# SparkFun_Digi_XBee_Regulated_Qwiic.net
KiCad netlist of a schematic drawn in EAGLE
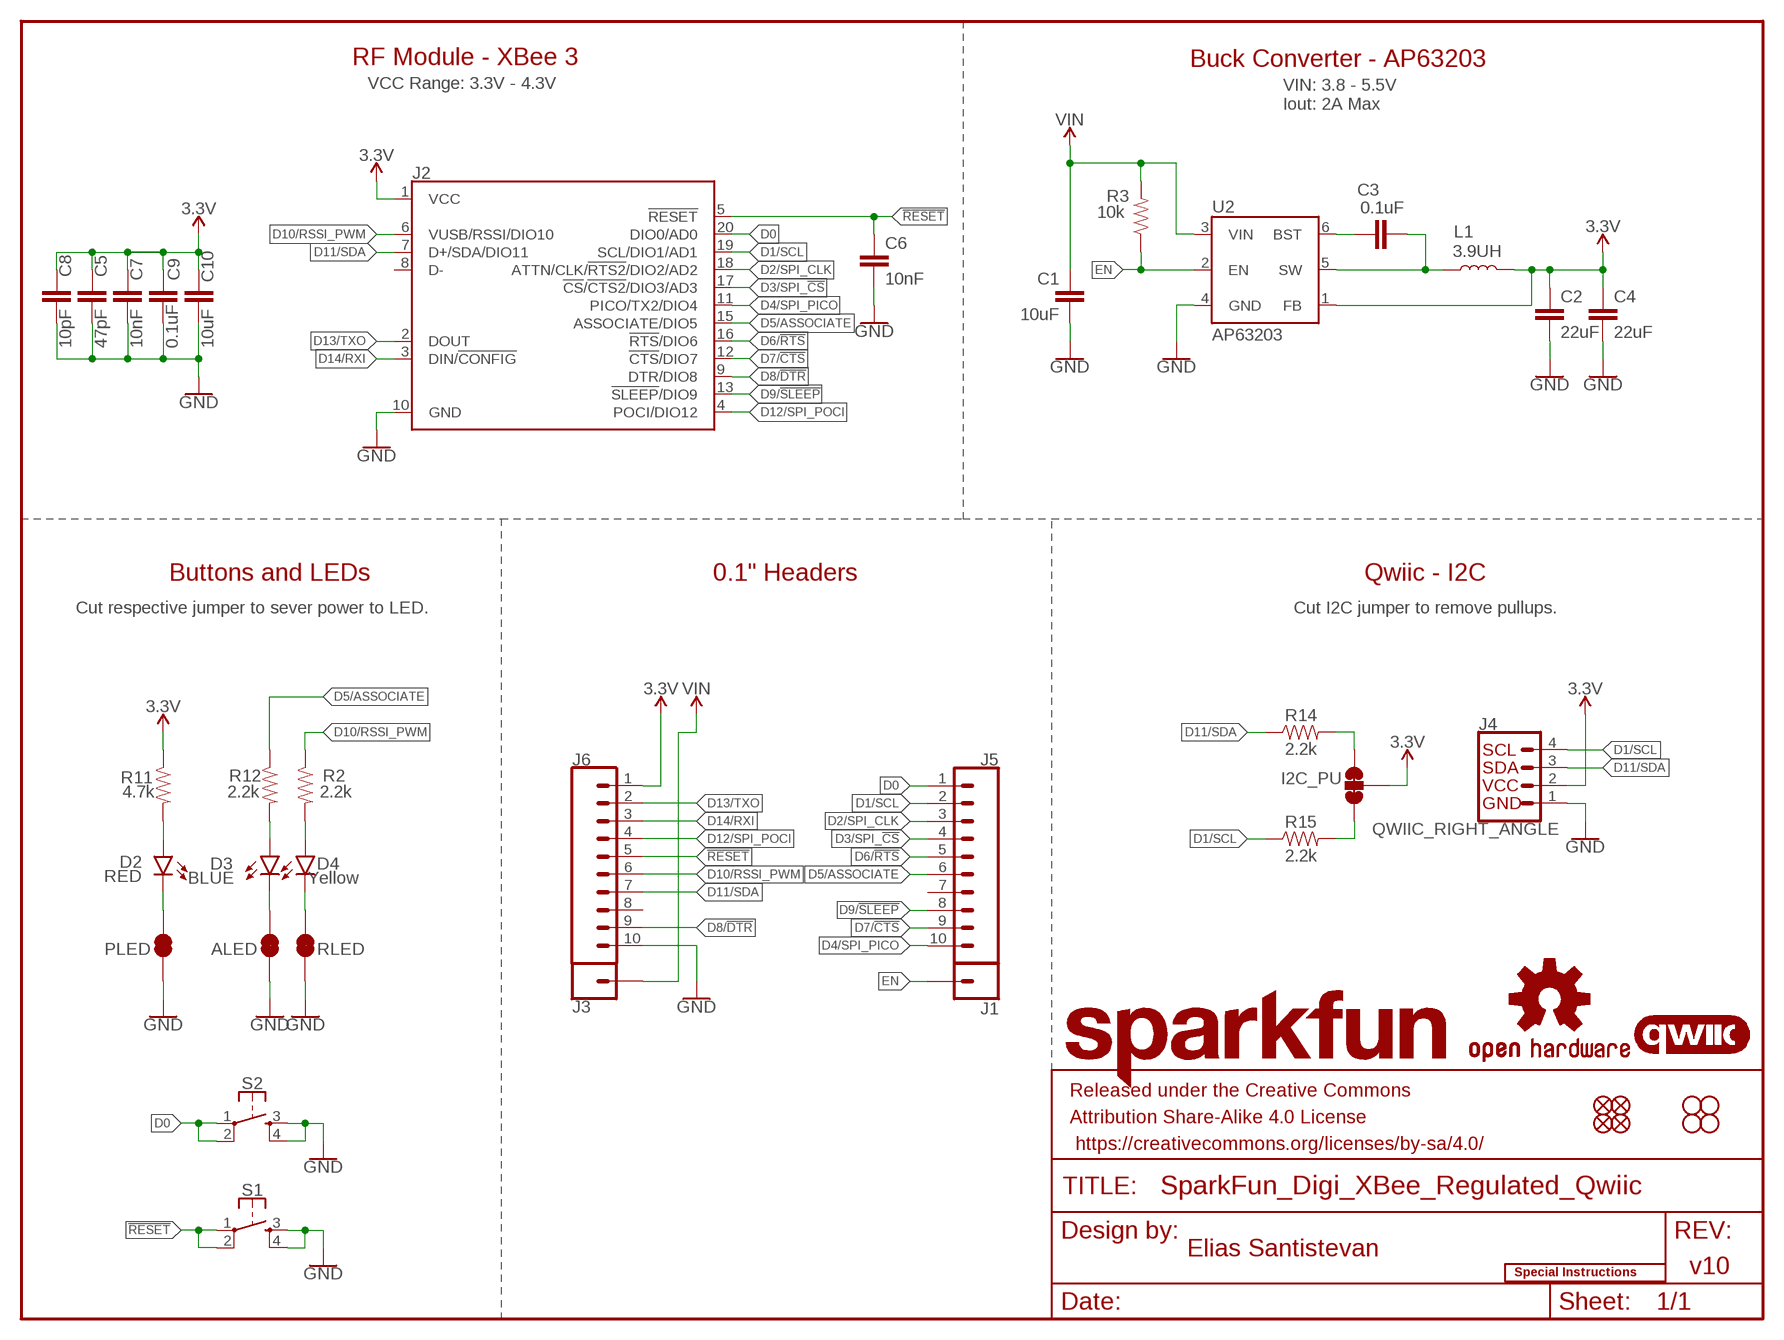
[diagram p0: schematic, sheet 1]

(export (version "E")
  (design (tool "Eeschema 10.0.6"))
  (components
    (comp (ref "ALED")
      (value "JUMPER-SMT_2_NC_TRACE_SILK")
      (footprint "eagle-import:SMT-JUMPER_2_NC_TRACE_SILK")
      (libsource (lib "eagle-import") (part "JUMPER-SMT_2_NC_TRACE_SILK"))
    )
    (comp (ref "C1")
      (value "10uF")
      (footprint "eagle-import:1210")
      (libsource (lib "eagle-import") (part "10UF-1210-50V-20%"))
    )
    (comp (ref "C2")
      (value "22uF")
      (footprint "eagle-import:0603")
      (libsource (lib "eagle-import") (part "22UF-0603-6.3V-20%"))
    )
    (comp (ref "C3")
      (value "0.1uF")
      (footprint "eagle-import:0603")
      (libsource (lib "eagle-import") (part "0.1UF-0603-25V-5%"))
    )
    (comp (ref "C4")
      (value "22uF")
      (footprint "eagle-import:0603")
      (libsource (lib "eagle-import") (part "22UF-0603-6.3V-20%"))
    )
    (comp (ref "C5")
      (value "47pF")
      (footprint "eagle-import:0603")
      (libsource (lib "eagle-import") (part "47PF-0603-50V-5%"))
    )
    (comp (ref "C6")
      (value "10nF")
      (footprint "eagle-import:0603")
      (libsource (lib "eagle-import") (part "10NF-0603-50V-10%"))
    )
    (comp (ref "C7")
      (value "10nF")
      (footprint "eagle-import:0603")
      (libsource (lib "eagle-import") (part "10NF-0603-50V-10%"))
    )
    (comp (ref "C8")
      (value "10pF")
      (footprint "eagle-import:0603")
      (libsource (lib "eagle-import") (part "10PF-0603-50V-5%"))
    )
    (comp (ref "C9")
      (value "0.1uF")
      (footprint "eagle-import:0603")
      (libsource (lib "eagle-import") (part "0.1UF-0603-25V-(+80/-20%)"))
    )
    (comp (ref "C10")
      (value "10uF")
      (footprint "eagle-import:0603")
      (libsource (lib "eagle-import") (part "10UF-0603-6.3V-20%"))
    )
    (comp (ref "D2")
      (value "RED")
      (footprint "eagle-import:LED-0603")
      (libsource (lib "eagle-import") (part "LED-RED_0603-KB"))
    )
    (comp (ref "D3")
      (value "BLUE")
      (footprint "eagle-import:LED-0603")
      (libsource (lib "eagle-import") (part "LED-BLUE0603"))
    )
    (comp (ref "D4")
      (value "Yellow")
      (footprint "eagle-import:LED-0603")
      (libsource (lib "eagle-import") (part "LED-YELLOW0603"))
    )
    (comp (ref "FD1")
      (value "FIDUCIAL1X2")
      (footprint "eagle-import:FIDUCIAL-1X2")
      (libsource (lib "eagle-import") (part "FIDUCIAL1X2"))
    )
    (comp (ref "FD2")
      (value "FIDUCIAL1X2")
      (footprint "eagle-import:FIDUCIAL-1X2")
      (libsource (lib "eagle-import") (part "FIDUCIAL1X2"))
    )
    (comp (ref "FD3")
      (value "FIDUCIAL1X2")
      (footprint "eagle-import:FIDUCIAL-1X2")
      (libsource (lib "eagle-import") (part "FIDUCIAL1X2"))
    )
    (comp (ref "FD4")
      (value "FIDUCIAL1X2")
      (footprint "eagle-import:FIDUCIAL-1X2")
      (libsource (lib "eagle-import") (part "FIDUCIAL1X2"))
    )
    (comp (ref "FRAME2")
      (value "FRAME-LETTER")
      (footprint "eagle-import:CREATIVE_COMMONS")
      (libsource (lib "eagle-import") (part "FRAME-LETTER"))
    )
    (comp (ref "H1")
      (value "STAND-OFFTIGHT")
      (footprint "eagle-import:STAND-OFF-TIGHT")
      (libsource (lib "eagle-import") (part "STAND-OFFTIGHT"))
    )
    (comp (ref "H2")
      (value "STAND-OFFTIGHT")
      (footprint "eagle-import:STAND-OFF-TIGHT")
      (libsource (lib "eagle-import") (part "STAND-OFFTIGHT"))
    )
    (comp (ref "H3")
      (value "STAND-OFFTIGHT")
      (footprint "eagle-import:STAND-OFF-TIGHT")
      (libsource (lib "eagle-import") (part "STAND-OFFTIGHT"))
    )
    (comp (ref "H4")
      (value "STAND-OFFTIGHT")
      (footprint "eagle-import:STAND-OFF-TIGHT")
      (libsource (lib "eagle-import") (part "STAND-OFFTIGHT"))
    )
    (comp (ref "I2C_PU")
      (value "JUMPER-SMT_3_2-NC_TRACE_SILK")
      (footprint "eagle-import:SMT-JUMPER_3_2-NC_TRACE_SILK")
      (libsource (lib "eagle-import") (part "JUMPER-SMT_3_2-NC_TRACE_SILK"))
    )
    (comp (ref "J1")
      (value "CONN_01PTH_NO_SILK_STAND")
      (footprint "eagle-import:1X01_NO_SILK_STAND")
      (libsource (lib "eagle-import") (part "CONN_01PTH_NO_SILK_STAND"))
    )
    (comp (ref "J2")
      (value "XBEE_UPDATEXBEE_SMD")
      (footprint "eagle-import:XBEE3-SMD")
      (libsource (lib "eagle-import") (part "XBEE_UPDATEXBEE_SMD"))
    )
    (comp (ref "J3")
      (value "CONN_01PTH_NO_SILK_STAND")
      (footprint "eagle-import:1X01_NO_SILK_STAND")
      (libsource (lib "eagle-import") (part "CONN_01PTH_NO_SILK_STAND"))
    )
    (comp (ref "J4")
      (value "QWIIC_RIGHT_ANGLE")
      (footprint "eagle-import:JST04_1MM_RA")
      (libsource (lib "eagle-import") (part "QWIIC_CONNECTORJS-1MM"))
    )
    (comp (ref "J5")
      (value "CONN_10NO_SILK_PTH_FEMALE")
      (footprint "eagle-import:1X10_NO_SILK")
      (libsource (lib "eagle-import") (part "CONN_10NO_SILK_PTH_FEMALE"))
    )
    (comp (ref "J6")
      (value "CONN_10NO_SILK_PTH_FEMALE")
      (footprint "eagle-import:1X10_NO_SILK")
      (libsource (lib "eagle-import") (part "CONN_10NO_SILK_PTH_FEMALE"))
    )
    (comp (ref "L1")
      (value "3.9UH")
      (footprint "eagle-import:INDUCTOR_3.9UH")
      (libsource (lib "eagle-import") (part "3.9UH"))
    )
    (comp (ref "LOGO1")
      (value "SPECIAL_INSTRUCTIONS-ORDERING")
      (footprint "eagle-import:ORDERING_INSTRUCTIONS")
      (libsource (lib "eagle-import") (part "SPECIAL_INSTRUCTIONS-ORDERING"))
    )
    (comp (ref "LOGO2")
      (value "OSHW-LOGOS")
      (footprint "eagle-import:OSHW-LOGO-S")
      (libsource (lib "eagle-import") (part "OSHW-LOGOS"))
    )
    (comp (ref "LOGO3")
      (value "QWIIC_LOGO_4MM")
      (footprint "eagle-import:QWIIC_4MM")
      (libsource (lib "eagle-import") (part "QWIIC_LOGO_4MM"))
    )
    (comp (ref "LOGO4")
      (value "SFE_LOGO_NAMEBLANK")
      (footprint "eagle-import:BLANK")
      (libsource (lib "eagle-import") (part "SFE_LOGO_NAMEBLANK"))
    )
    (comp (ref "PLED")
      (value "JUMPER-SMT_2_NC_TRACE_SILK")
      (footprint "eagle-import:SMT-JUMPER_2_NC_TRACE_SILK")
      (libsource (lib "eagle-import") (part "JUMPER-SMT_2_NC_TRACE_SILK"))
    )
    (comp (ref "R2")
      (value "2.2k")
      (footprint "eagle-import:0603")
      (libsource (lib "eagle-import") (part "2.2KOHM-0603-1/10W-1%"))
    )
    (comp (ref "R3")
      (value "10k")
      (footprint "eagle-import:0603")
      (libsource (lib "eagle-import") (part "10KOHM-0603-1/10W-1%"))
    )
    (comp (ref "R11")
      (value "4.7k")
      (footprint "eagle-import:0603")
      (libsource (lib "eagle-import") (part "4.7KOHM-0603-1/10W-1%"))
    )
    (comp (ref "R12")
      (value "2.2k")
      (footprint "eagle-import:0603")
      (libsource (lib "eagle-import") (part "2.2KOHM-0603-1/10W-1%"))
    )
    (comp (ref "R14")
      (value "2.2k")
      (footprint "eagle-import:0603")
      (libsource (lib "eagle-import") (part "2.2KOHM-0603-1/10W-1%"))
    )
    (comp (ref "R15")
      (value "2.2k")
      (footprint "eagle-import:0603")
      (libsource (lib "eagle-import") (part "2.2KOHM-0603-1/10W-1%"))
    )
    (comp (ref "RLED")
      (value "JUMPER-SMT_2_NC_TRACE_SILK")
      (footprint "eagle-import:SMT-JUMPER_2_NC_TRACE_SILK")
      (libsource (lib "eagle-import") (part "JUMPER-SMT_2_NC_TRACE_SILK"))
    )
    (comp (ref "S1")
      (value "MOMENTARY-SWITCH-SPST-2-SMD-5.2MM-TALL")
      (footprint "eagle-import:TACTILE_SWITCH_SMD_5.2MM")
      (libsource (lib "eagle-import") (part "MOMENTARY-SWITCH-SPST-2-SMD-5.2MM-TALL"))
    )
    (comp (ref "S2")
      (value "MOMENTARY-SWITCH-SPST-2-SMD-5.2MM-TALL")
      (footprint "eagle-import:TACTILE_SWITCH_SMD_5.2MM")
      (libsource (lib "eagle-import") (part "MOMENTARY-SWITCH-SPST-2-SMD-5.2MM-TALL"))
    )
    (comp (ref "U2")
      (value "AP63203")
      (footprint "eagle-import:SOT23-6")
      (libsource (lib "eagle-import") (part "AP63203"))
    )
  )
  (nets
    (net (code "1") (name "/D3{slash}SPI_~{CS}") (class "Default")
      (node (ref "J2") (pin "17") (pinfunction "~{CS}/~{CTS2}/DIO3/AD3_17") (pintype "bidirectional"))
      (node (ref "J5") (pin "4") (pinfunction "4_4") (pintype "passive"))
    )
    (net (code "2") (name "/D6{slash}~{RTS}") (class "Default")
      (node (ref "J2") (pin "16") (pinfunction "~{RTS}/DIO6_16") (pintype "input"))
      (node (ref "J5") (pin "5") (pinfunction "5_5") (pintype "passive"))
    )
    (net (code "3") (name "/D7{slash}~{CTS}") (class "Default")
      (node (ref "J2") (pin "12") (pinfunction "~{CTS}/DIO7_12") (pintype "output"))
      (node (ref "J5") (pin "9") (pinfunction "9_9") (pintype "passive"))
    )
    (net (code "4") (name "/D8{slash}~{DTR}") (class "Default")
      (node (ref "J2") (pin "9") (pinfunction "DTR/DIO8_9") (pintype "bidirectional"))
      (node (ref "J6") (pin "9") (pinfunction "9_9") (pintype "passive"))
    )
    (net (code "5") (name "/D9{slash}~{SLEEP}") (class "Default")
      (node (ref "J2") (pin "13") (pinfunction "~{SLEEP}/DIO9_13") (pintype "bidirectional"))
      (node (ref "J5") (pin "8") (pinfunction "8_8") (pintype "passive"))
    )
    (net (code "6") (name "/~{RESET}") (class "Default")
      (node (ref "C6") (pin "1") (pinfunction "1_1") (pintype "passive"))
      (node (ref "J2") (pin "5") (pinfunction "~{RESET}_5") (pintype "input"))
      (node (ref "J6") (pin "5") (pinfunction "5_5") (pintype "passive"))
      (node (ref "S1") (pin "1") (pinfunction "1_1") (pintype "passive"))
      (node (ref "S1") (pin "2") (pinfunction "2_2") (pintype "passive"))
    )
    (net (code "7") (name "3.3V") (class "Default")
      (node (ref "C10") (pin "1") (pinfunction "1_1") (pintype "passive"))
      (node (ref "C2") (pin "1") (pinfunction "1_1") (pintype "passive"))
      (node (ref "C4") (pin "1") (pinfunction "1_1") (pintype "passive"))
      (node (ref "C5") (pin "1") (pinfunction "1_1") (pintype "passive"))
      (node (ref "C7") (pin "1") (pinfunction "1_1") (pintype "passive"))
      (node (ref "C8") (pin "1") (pinfunction "1_1") (pintype "passive"))
      (node (ref "C9") (pin "1") (pinfunction "1_1") (pintype "passive"))
      (node (ref "I2C_PU") (pin "2") (pinfunction "2_2") (pintype "passive"))
      (node (ref "J2") (pin "1") (pinfunction "VCC_1") (pintype "power_in"))
      (node (ref "J4") (pin "2") (pinfunction "2_2") (pintype "power_in"))
      (node (ref "J6") (pin "1") (pinfunction "1_1") (pintype "passive"))
      (node (ref "L1") (pin "P$2") (pinfunction "2_P$2") (pintype "passive"))
      (node (ref "R11") (pin "1") (pinfunction "1_1") (pintype "passive"))
      (node (ref "U2") (pin "1") (pinfunction "FB_1") (pintype "bidirectional"))
    )
    (net (code "8") (name "D0") (class "Default")
      (node (ref "J2") (pin "20") (pinfunction "DIO0/AD0_20") (pintype "bidirectional"))
      (node (ref "J5") (pin "1") (pinfunction "1_1") (pintype "passive"))
      (node (ref "S2") (pin "1") (pinfunction "1_1") (pintype "passive"))
      (node (ref "S2") (pin "2") (pinfunction "2_2") (pintype "passive"))
    )
    (net (code "9") (name "D1{slash}SCL") (class "Default")
      (node (ref "J2") (pin "19") (pinfunction "SCL/DIO1/AD1_19") (pintype "bidirectional"))
      (node (ref "J4") (pin "4") (pinfunction "4_4") (pintype "passive"))
      (node (ref "J5") (pin "2") (pinfunction "2_2") (pintype "passive"))
      (node (ref "R15") (pin "1") (pinfunction "1_1") (pintype "passive"))
    )
    (net (code "10") (name "D2{slash}SPI_CLK") (class "Default")
      (node (ref "J2") (pin "18") (pinfunction "ATTN/CLK/~{RTS2}/DIO2/AD2_18") (pintype "bidirectional"))
      (node (ref "J5") (pin "3") (pinfunction "3_3") (pintype "passive"))
    )
    (net (code "11") (name "D4{slash}SPI_PICO") (class "Default")
      (node (ref "J2") (pin "11") (pinfunction "PICO/TX2/DIO4_11") (pintype "bidirectional"))
      (node (ref "J5") (pin "10") (pinfunction "10_10") (pintype "passive"))
    )
    (net (code "12") (name "D5{slash}ASSOCIATE") (class "Default")
      (node (ref "J2") (pin "15") (pinfunction "ASSOCIATE/DIO5_15") (pintype "bidirectional"))
      (node (ref "J5") (pin "6") (pinfunction "6_6") (pintype "passive"))
      (node (ref "R12") (pin "1") (pinfunction "1_1") (pintype "passive"))
    )
    (net (code "13") (name "D10{slash}RSSI_PWM") (class "Default")
      (node (ref "J2") (pin "6") (pinfunction "VUSB/RSSI/DIO10_6") (pintype "bidirectional"))
      (node (ref "J6") (pin "6") (pinfunction "6_6") (pintype "passive"))
      (node (ref "R2") (pin "1") (pinfunction "1_1") (pintype "passive"))
    )
    (net (code "14") (name "D11{slash}SDA") (class "Default")
      (node (ref "J2") (pin "7") (pinfunction "D+/SDA/DIO11_7") (pintype "bidirectional"))
      (node (ref "J4") (pin "3") (pinfunction "3_3") (pintype "passive"))
      (node (ref "J6") (pin "7") (pinfunction "7_7") (pintype "passive"))
      (node (ref "R14") (pin "1") (pinfunction "1_1") (pintype "passive"))
    )
    (net (code "15") (name "D12{slash}SPI_POCI") (class "Default")
      (node (ref "J2") (pin "4") (pinfunction "POCI/DIO12_4") (pintype "bidirectional"))
      (node (ref "J6") (pin "4") (pinfunction "4_4") (pintype "passive"))
    )
    (net (code "16") (name "D13{slash}TXO") (class "Default")
      (node (ref "J2") (pin "2") (pinfunction "DOUT_2") (pintype "output"))
      (node (ref "J6") (pin "2") (pinfunction "2_2") (pintype "passive"))
    )
    (net (code "17") (name "D14{slash}RXI") (class "Default")
      (node (ref "J2") (pin "3") (pinfunction "DIN/~{CONFIG}_3") (pintype "input"))
      (node (ref "J6") (pin "3") (pinfunction "3_3") (pintype "passive"))
    )
    (net (code "18") (name "EN") (class "Default")
      (node (ref "J1") (pin "1") (pinfunction "1_1") (pintype "passive"))
      (node (ref "R3") (pin "1") (pinfunction "1_1") (pintype "passive"))
      (node (ref "U2") (pin "2") (pinfunction "EN_2") (pintype "bidirectional"))
    )
    (net (code "19") (name "GND") (class "Default")
      (node (ref "ALED") (pin "1") (pinfunction "1_1") (pintype "passive"))
      (node (ref "C1") (pin "2") (pinfunction "2_2") (pintype "passive"))
      (node (ref "C10") (pin "2") (pinfunction "2_2") (pintype "passive"))
      (node (ref "C2") (pin "2") (pinfunction "2_2") (pintype "passive"))
      (node (ref "C4") (pin "2") (pinfunction "2_2") (pintype "passive"))
      (node (ref "C5") (pin "2") (pinfunction "2_2") (pintype "passive"))
      (node (ref "C6") (pin "2") (pinfunction "2_2") (pintype "passive"))
      (node (ref "C7") (pin "2") (pinfunction "2_2") (pintype "passive"))
      (node (ref "C8") (pin "2") (pinfunction "2_2") (pintype "passive"))
      (node (ref "C9") (pin "2") (pinfunction "2_2") (pintype "passive"))
      (node (ref "J2") (pin "10") (pinfunction "GND_10") (pintype "power_in"))
      (node (ref "J4") (pin "1") (pinfunction "1_1") (pintype "power_in"))
      (node (ref "J6") (pin "10") (pinfunction "10_10") (pintype "passive"))
      (node (ref "PLED") (pin "1") (pinfunction "1_1") (pintype "passive"))
      (node (ref "RLED") (pin "1") (pinfunction "1_1") (pintype "passive"))
      (node (ref "S1") (pin "3") (pinfunction "3_3") (pintype "passive"))
      (node (ref "S1") (pin "4") (pinfunction "4_4") (pintype "passive"))
      (node (ref "S2") (pin "3") (pinfunction "3_3") (pintype "passive"))
      (node (ref "S2") (pin "4") (pinfunction "4_4") (pintype "passive"))
      (node (ref "U2") (pin "4") (pinfunction "GND_4") (pintype "bidirectional"))
    )
    (net (code "20") (name "Net-(ALED-Pad2)") (class "Default")
      (node (ref "ALED") (pin "2") (pinfunction "2_2") (pintype "passive"))
      (node (ref "D3") (pin "C") (pinfunction "C_C") (pintype "passive"))
    )
    (net (code "21") (name "Net-(D2-PadA)") (class "Default")
      (node (ref "D2") (pin "A") (pinfunction "A_A") (pintype "passive"))
      (node (ref "R11") (pin "2") (pinfunction "2_2") (pintype "passive"))
    )
    (net (code "22") (name "Net-(D2-PadC)") (class "Default")
      (node (ref "D2") (pin "C") (pinfunction "C_C") (pintype "passive"))
      (node (ref "PLED") (pin "2") (pinfunction "2_2") (pintype "passive"))
    )
    (net (code "23") (name "Net-(D3-PadA)") (class "Default")
      (node (ref "D3") (pin "A") (pinfunction "A_A") (pintype "passive"))
      (node (ref "R12") (pin "2") (pinfunction "2_2") (pintype "passive"))
    )
    (net (code "24") (name "Net-(D4-PadA)") (class "Default")
      (node (ref "D4") (pin "A") (pinfunction "A_A") (pintype "passive"))
      (node (ref "R2") (pin "2") (pinfunction "2_2") (pintype "passive"))
    )
    (net (code "25") (name "Net-(D4-PadC)") (class "Default")
      (node (ref "D4") (pin "C") (pinfunction "C_C") (pintype "passive"))
      (node (ref "RLED") (pin "2") (pinfunction "2_2") (pintype "passive"))
    )
    (net (code "26") (name "Net-(I2C_PU-Pad1)") (class "Default")
      (node (ref "I2C_PU") (pin "1") (pinfunction "1_1") (pintype "passive"))
      (node (ref "R15") (pin "2") (pinfunction "2_2") (pintype "passive"))
    )
    (net (code "27") (name "Net-(I2C_PU-Pad3)") (class "Default")
      (node (ref "I2C_PU") (pin "3") (pinfunction "3_3") (pintype "passive"))
      (node (ref "R14") (pin "2") (pinfunction "2_2") (pintype "passive"))
    )
    (net (code "28") (name "Net-(L1-1)") (class "Default")
      (node (ref "C3") (pin "2") (pinfunction "2_2") (pintype "passive"))
      (node (ref "L1") (pin "P$1") (pinfunction "1_P$1") (pintype "passive"))
      (node (ref "U2") (pin "5") (pinfunction "SW_5") (pintype "bidirectional"))
    )
    (net (code "29") (name "Net-(U2-BST)") (class "Default")
      (node (ref "C3") (pin "1") (pinfunction "1_1") (pintype "passive"))
      (node (ref "U2") (pin "6") (pinfunction "BST_6") (pintype "bidirectional"))
    )
    (net (code "30") (name "VIN") (class "Default")
      (node (ref "C1") (pin "1") (pinfunction "1_1") (pintype "passive"))
      (node (ref "J3") (pin "1") (pinfunction "1_1") (pintype "passive"))
      (node (ref "R3") (pin "2") (pinfunction "2_2") (pintype "passive"))
      (node (ref "U2") (pin "3") (pinfunction "VIN_3") (pintype "bidirectional"))
    )
    (net (code "31") (name "unconnected-(J2-D--Pad8)") (class "Default")
      (node (ref "J2") (pin "8") (pinfunction "D-_8") (pintype "bidirectional"))
    )
    (net (code "32") (name "unconnected-(J5-Pad7)") (class "Default")
      (node (ref "J5") (pin "7") (pinfunction "7_7") (pintype "passive"))
    )
    (net (code "33") (name "unconnected-(J6-Pad8)") (class "Default")
      (node (ref "J6") (pin "8") (pinfunction "8_8") (pintype "passive"))
    )
  )
)
